# MCU.net
KiCad netlist of a schematic drawn in Altium Designer
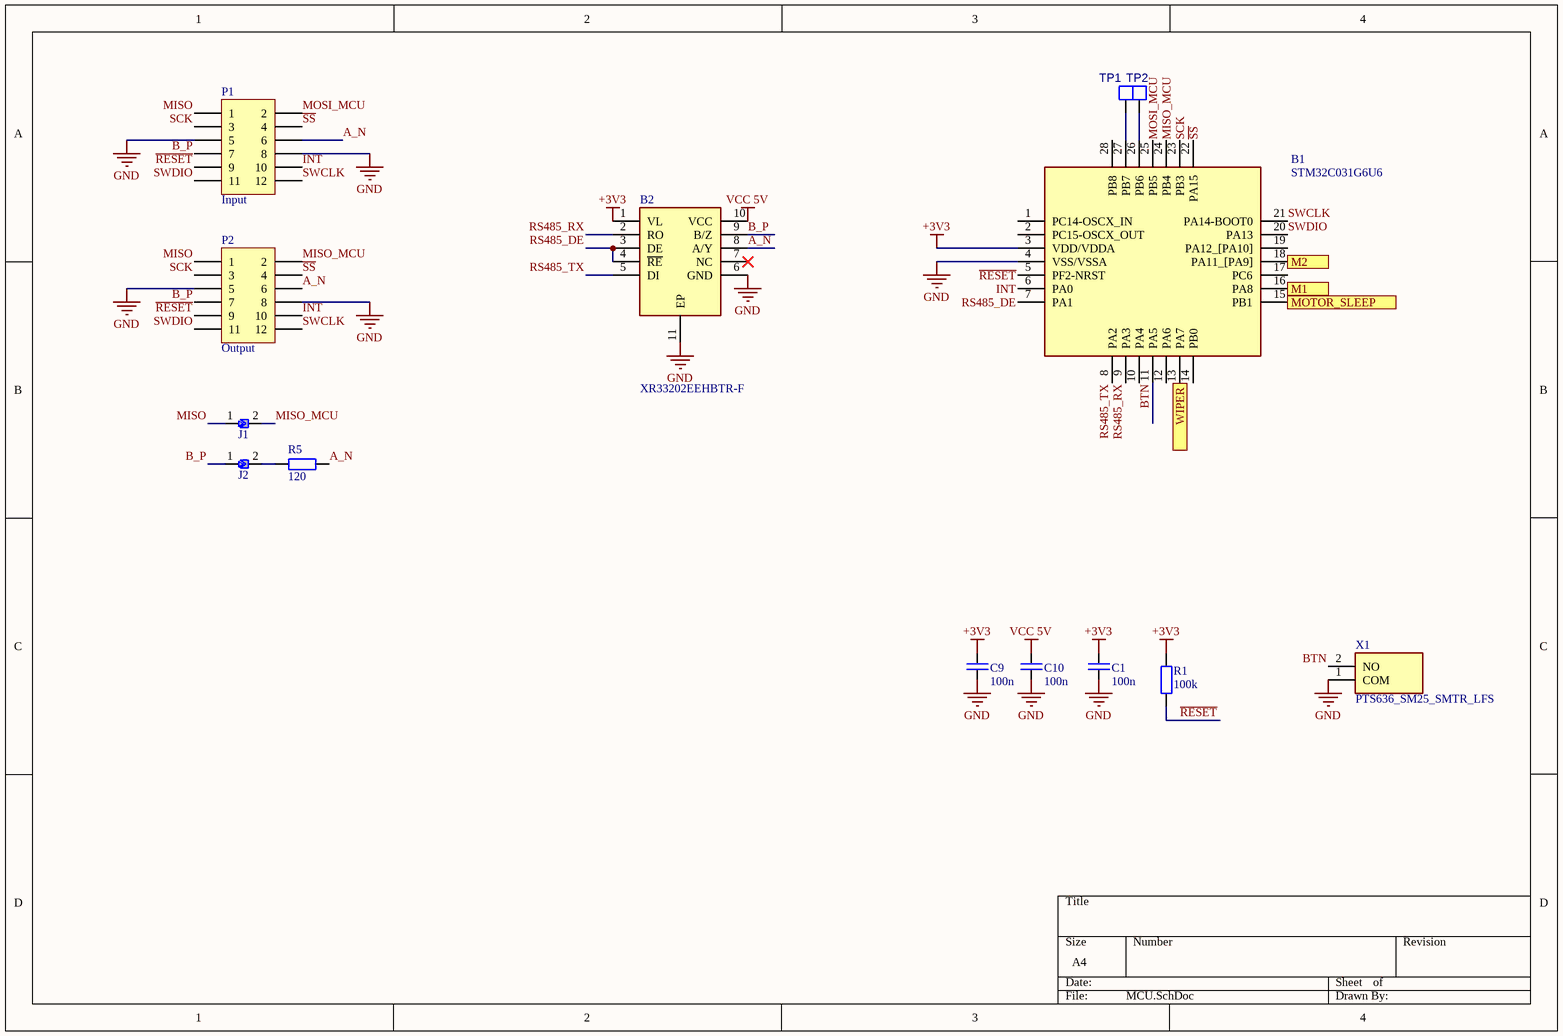
[diagram p0: MCU.SchDoc]

(export (version "E")
  (design (tool "Eeschema 10.0.6"))
  (components
    (comp (ref "B1")
      (value "STM32C031G6U6")
      (footprint "QFN50P400X400X60-28N-D")
      (fields (field (name "MOUSER PART NUMBER") "511-STM32C031G6U6"))
      (libsource (lib "components_library") (part "STM32C031G6U6"))
    )
    (comp (ref "B2")
      (value "XR33202EEHBTR-F")
      (footprint "SON50P300X300X80-11N-D")
      (description "RS-422/RS-485 Interface IC Wide Supply Trans with I/O Interface")
      (fields (field (name "MOUSER PART NUMBER") "701-XR33202EEHBTR-F"))
      (libsource (lib "components_library") (part "XR33202EEHBTR-F"))
    )
    (comp (ref "C1")
      (value "100n")
      (footprint "R1005_0402i_L")
      (description "Capacitor")
      (libsource (lib "General") (part "C"))
    )
    (comp (ref "C9")
      (value "100n")
      (footprint "R1005_0402i_L")
      (description "Capacitor")
      (libsource (lib "General") (part "C"))
    )
    (comp (ref "C10")
      (value "100n")
      (footprint "R1005_0402i_L")
      (description "Capacitor")
      (libsource (lib "General") (part "C"))
    )
    (comp (ref "J1")
      (value "solder_jumper")
      (footprint "solder_jumper_triangle")
      (libsource (lib "components_library") (part "solder_jumper"))
    )
    (comp (ref "J2")
      (value "solder_jumper")
      (footprint "solder_jumper_triangle")
      (libsource (lib "components_library") (part "solder_jumper"))
    )
    (comp (ref "P1")
      (value "Input")
      (footprint "1.27mm SMD conn")
      (description "Header, 6-Pin, Dual row")
      (fields (field (name "PUBLISHER") "Altium Limited"))
      (libsource (lib "Miscellaneous Connectors") (part "Header 6X2"))
    )
    (comp (ref "P2")
      (value "Output")
      (footprint "1.27mm SMD conn")
      (description "Header, 6-Pin, Dual row")
      (fields (field (name "PUBLISHER") "Altium Limited"))
      (libsource (lib "Miscellaneous Connectors") (part "Header 6X2"))
    )
    (comp (ref "R1")
      (value "100k")
      (footprint "R1005_0402i_L")
      (description "R")
      (libsource (lib "General") (part "R"))
    )
    (comp (ref "R5")
      (value "120")
      (footprint "R1005_0402i_L")
      (description "R")
      (libsource (lib "General") (part "R"))
    )
    (comp (ref "TP1") (value "PAD") (footprint "PAD") (libsource (lib "General") (part "PAD")))
    (comp (ref "TP2") (value "PAD") (footprint "PAD") (libsource (lib "General") (part "PAD")))
    (comp (ref "X1")
      (value "PTS636_SM25_SMTR_LFS")
      (footprint "PTS636SM25SMTRLFS")
      (description "Tactile Switches Tact 50mA 12VDC, 6.0x3.5, 2.5mm H, 180gf, G leads, No ground pin, White Actuator")
      (fields
        (field (name "MOUSER PART NUMBER") "611-PTS636SM25SMTRLF")
        (field (name "MANUFACTURER_PART_NUMBER") "PTS636 SM25 SMTR LFS")
      )
      (libsource (lib "components_library") (part "PTS636_SM25_SMTR_LFS"))
    )
  )
  (nets
    (net (code "1") (name "+3V3") (class "Default")
      (node (ref "B1") (pin "3") (pinfunction "VDD/VDDA_3") (pintype "passive"))
      (node (ref "B2") (pin "1") (pinfunction "VL_1") (pintype "passive"))
      (node (ref "C1") (pin "1") (pinfunction "1_1") (pintype "passive"))
      (node (ref "C9") (pin "1") (pinfunction "1_1") (pintype "passive"))
      (node (ref "R1") (pin "1") (pintype "passive"))
    )
    (net (code "2") (name "/A_N") (class "Default")
      (node (ref "B2") (pin "8") (pinfunction "A/Y_8") (pintype "passive"))
      (node (ref "P1") (pin "6") (pinfunction "6_6") (pintype "passive"))
      (node (ref "P2") (pin "6") (pinfunction "6_6") (pintype "passive"))
      (node (ref "R5") (pin "2") (pintype "passive"))
    )
    (net (code "3") (name "/BTN") (class "Default")
      (node (ref "B1") (pin "11") (pinfunction "PA5_11") (pintype "passive"))
      (node (ref "X1") (pin "2") (pinfunction "NO_2") (pintype "passive"))
    )
    (net (code "4") (name "/B_P") (class "Default")
      (node (ref "B2") (pin "9") (pinfunction "B/Z_9") (pintype "passive"))
      (node (ref "J2") (pin "1") (pintype "passive"))
      (node (ref "P1") (pin "7") (pinfunction "7_7") (pintype "passive"))
      (node (ref "P2") (pin "7") (pinfunction "7_7") (pintype "passive"))
    )
    (net (code "5") (name "/INT") (class "Default")
      (node (ref "B1") (pin "6") (pinfunction "PA0_6") (pintype "passive"))
      (node (ref "P1") (pin "10") (pinfunction "10_10") (pintype "passive"))
      (node (ref "P2") (pin "10") (pinfunction "10_10") (pintype "passive"))
    )
    (net (code "6") (name "/M1") (class "Default")
      (node (ref "B1") (pin "16") (pinfunction "PA8_16") (pintype "passive"))
    )
    (net (code "7") (name "/M2") (class "Default")
      (node (ref "B1") (pin "18") (pinfunction "PA11_[PA9]_18") (pintype "passive"))
    )
    (net (code "8") (name "/MISO") (class "Default")
      (node (ref "J1") (pin "1") (pintype "passive"))
      (node (ref "P1") (pin "1") (pinfunction "1_1") (pintype "passive"))
      (node (ref "P2") (pin "1") (pinfunction "1_1") (pintype "passive"))
    )
    (net (code "9") (name "/MISO_MCU") (class "Default")
      (node (ref "B1") (pin "24") (pinfunction "PB4_24") (pintype "passive"))
      (node (ref "J1") (pin "2") (pintype "passive"))
      (node (ref "P2") (pin "2") (pinfunction "2_2") (pintype "passive"))
    )
    (net (code "10") (name "/MOSI_MCU") (class "Default")
      (node (ref "B1") (pin "25") (pinfunction "PB5_25") (pintype "passive"))
      (node (ref "P1") (pin "2") (pinfunction "2_2") (pintype "passive"))
    )
    (net (code "11") (name "/MOTOR_SLEEP") (class "Default")
      (node (ref "B1") (pin "15") (pinfunction "PB1_15") (pintype "passive"))
    )
    (net (code "12") (name "/RS485_DE") (class "Default")
      (node (ref "B1") (pin "7") (pinfunction "PA1_7") (pintype "passive"))
      (node (ref "B2") (pin "3") (pinfunction "DE_3") (pintype "passive"))
      (node (ref "B2") (pin "4") (pinfunction "~{RE}_4") (pintype "passive"))
    )
    (net (code "13") (name "/RS485_RX") (class "Default")
      (node (ref "B1") (pin "9") (pinfunction "PA3_9") (pintype "passive"))
      (node (ref "B2") (pin "2") (pinfunction "RO_2") (pintype "passive"))
    )
    (net (code "14") (name "/RS485_TX") (class "Default")
      (node (ref "B1") (pin "8") (pinfunction "PA2_8") (pintype "passive"))
      (node (ref "B2") (pin "5") (pinfunction "DI_5") (pintype "passive"))
    )
    (net (code "15") (name "/SCK") (class "Default")
      (node (ref "B1") (pin "23") (pinfunction "PB3_23") (pintype "passive"))
      (node (ref "P1") (pin "3") (pinfunction "3_3") (pintype "passive"))
      (node (ref "P2") (pin "3") (pinfunction "3_3") (pintype "passive"))
    )
    (net (code "16") (name "/SWCLK") (class "Default")
      (node (ref "B1") (pin "21") (pinfunction "PA14-BOOT0_21") (pintype "passive"))
      (node (ref "P1") (pin "12") (pinfunction "12_12") (pintype "passive"))
      (node (ref "P2") (pin "12") (pinfunction "12_12") (pintype "passive"))
    )
    (net (code "17") (name "/SWDIO") (class "Default")
      (node (ref "B1") (pin "20") (pinfunction "PA13_20") (pintype "passive"))
      (node (ref "P1") (pin "11") (pinfunction "11_11") (pintype "passive"))
      (node (ref "P2") (pin "11") (pinfunction "11_11") (pintype "passive"))
    )
    (net (code "18") (name "/WIPER") (class "Default")
      (node (ref "B1") (pin "13") (pinfunction "PA7_13") (pintype "passive"))
    )
    (net (code "19") (name "/~{RESET}") (class "Default")
      (node (ref "B1") (pin "5") (pinfunction "PF2-NRST_5") (pintype "passive"))
      (node (ref "P1") (pin "9") (pinfunction "9_9") (pintype "passive"))
      (node (ref "P2") (pin "9") (pinfunction "9_9") (pintype "passive"))
      (node (ref "R1") (pin "2") (pintype "passive"))
    )
    (net (code "20") (name "/~{SS}") (class "Default")
      (node (ref "B1") (pin "22") (pinfunction "PA15_22") (pintype "passive"))
      (node (ref "P1") (pin "4") (pinfunction "4_4") (pintype "passive"))
      (node (ref "P2") (pin "4") (pinfunction "4_4") (pintype "passive"))
    )
    (net (code "21") (name "GND") (class "Default")
      (node (ref "B1") (pin "4") (pinfunction "VSS/VSSA_4") (pintype "passive"))
      (node (ref "B2") (pin "11") (pinfunction "EP_11") (pintype "passive"))
      (node (ref "B2") (pin "6") (pinfunction "GND_6") (pintype "passive"))
      (node (ref "C1") (pin "2") (pinfunction "2_2") (pintype "passive"))
      (node (ref "C10") (pin "2") (pinfunction "2_2") (pintype "passive"))
      (node (ref "C9") (pin "2") (pinfunction "2_2") (pintype "passive"))
      (node (ref "P1") (pin "5") (pinfunction "5_5") (pintype "passive"))
      (node (ref "P1") (pin "8") (pinfunction "8_8") (pintype "passive"))
      (node (ref "P2") (pin "5") (pinfunction "5_5") (pintype "passive"))
      (node (ref "P2") (pin "8") (pinfunction "8_8") (pintype "passive"))
      (node (ref "X1") (pin "1") (pinfunction "COM_1") (pintype "passive"))
    )
    (net (code "22") (name "Net-(B1-PB6)") (class "Default")
      (node (ref "B1") (pin "26") (pinfunction "PB6_26") (pintype "passive"))
      (node (ref "TP2") (pin "1") (pinfunction "1_1") (pintype "passive"))
    )
    (net (code "23") (name "Net-(B1-PB7)") (class "Default")
      (node (ref "B1") (pin "27") (pinfunction "PB7_27") (pintype "passive"))
      (node (ref "TP1") (pin "1") (pinfunction "1_1") (pintype "passive"))
    )
    (net (code "24") (name "Net-(J2-Pad2)") (class "Default")
      (node (ref "J2") (pin "2") (pintype "passive"))
      (node (ref "R5") (pin "1") (pintype "passive"))
    )
    (net (code "25") (name "VCC 5V") (class "Default")
      (node (ref "B2") (pin "10") (pinfunction "VCC_10") (pintype "passive"))
      (node (ref "C10") (pin "1") (pinfunction "1_1") (pintype "passive"))
    )
    (net (code "26") (name "unconnected-(B1-PA4-Pad10)") (class "Default")
      (node (ref "B1") (pin "10") (pinfunction "PA4_10") (pintype "passive"))
    )
    (net (code "27") (name "unconnected-(B1-PA6-Pad12)") (class "Default")
      (node (ref "B1") (pin "12") (pinfunction "PA6_12") (pintype "passive"))
    )
    (net (code "28") (name "unconnected-(B1-PA12_[PA10]-Pad19)") (class "Default")
      (node (ref "B1") (pin "19") (pinfunction "PA12_[PA10]_19") (pintype "passive"))
    )
    (net (code "29") (name "unconnected-(B1-PB0-Pad14)") (class "Default")
      (node (ref "B1") (pin "14") (pinfunction "PB0_14") (pintype "passive"))
    )
    (net (code "30") (name "unconnected-(B1-PB8-Pad28)") (class "Default")
      (node (ref "B1") (pin "28") (pinfunction "PB8_28") (pintype "passive"))
    )
    (net (code "31") (name "unconnected-(B1-PC6-Pad17)") (class "Default")
      (node (ref "B1") (pin "17") (pinfunction "PC6_17") (pintype "passive"))
    )
    (net (code "32") (name "unconnected-(B1-PC14-OSCX_IN-Pad1)") (class "Default")
      (node (ref "B1") (pin "1") (pinfunction "PC14-OSCX_IN_1") (pintype "passive"))
    )
    (net (code "33") (name "unconnected-(B1-PC15-OSCX_OUT-Pad2)") (class "Default")
      (node (ref "B1") (pin "2") (pinfunction "PC15-OSCX_OUT_2") (pintype "passive"))
    )
    (net (code "34") (name "unconnected-(B2-NC-Pad7)") (class "Default")
      (node (ref "B2") (pin "7") (pinfunction "NC_7") (pintype "passive+no_connect"))
    )
  )
)
